# LiPoBattery.net
KiCad netlist of a schematic drawn in Altium Designer
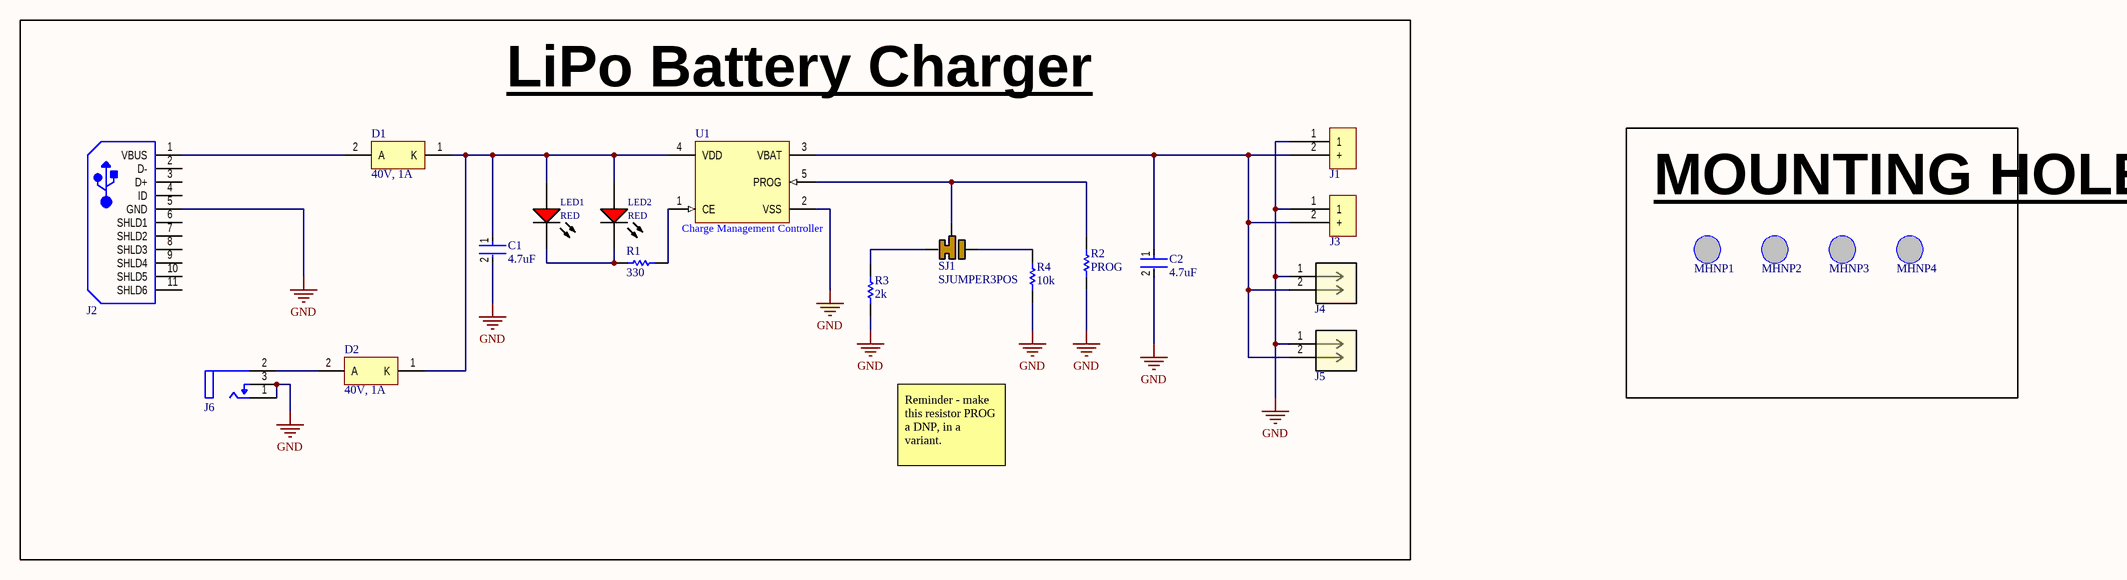
[diagram p0: LiPoBattery.SchDoc]

(export (version "E")
  (design (tool "Eeschema 10.0.6"))
  (components
    (comp (ref "C1")
      (value "4.7uF")
      (footprint "FP-CC0805-0_85-MFG")
      (description "4.7µF ±10% 6.3V Ceramic Capacitor X7R 0805 (2012 Metric)")
      (fields (field (name "MANUFACTURER") "Yageo") (field (name "TOLERANCE") "0.1"))
      (libsource (lib "LiPoBattery_A") (part "CAP CER 4.7UF 6.3V X7R 0805"))
    )
    (comp (ref "C2")
      (value "4.7uF")
      (footprint "FP-CC0805-0_85-MFG")
      (description "4.7µF ±10% 6.3V Ceramic Capacitor X7R 0805 (2012 Metric)")
      (fields (field (name "MANUFACTURER") "Yageo") (field (name "TOLERANCE") "0.1"))
      (libsource (lib "LiPoBattery_A") (part "CAP CER 4.7UF 6.3V X7R 0805"))
    )
    (comp (ref "D1")
      (value "40V, 1A")
      (footprint "ONSC-SMA-2-403D-02_V")
      (description "Schottky Power Rectifier, 2-Pin SMA, Pb-Free, Cut Tape, Diode Schottky 40V 1A Surface Mount SMA")
      (fields (field (name "PARTNUMBER") "MBRA140T3G") (field (name "MANUFACTURER") "ON Semiconductor"))
      (libsource (lib "LiPoBattery_A") (part "DIODE SCHOTTKY 40V 1A SMA"))
    )
    (comp (ref "D2")
      (value "40V, 1A")
      (footprint "ONSC-SMA-2-403D-02_V")
      (description "Schottky Power Rectifier, 2-Pin SMA, Pb-Free, Cut Tape, Diode Schottky 40V 1A Surface Mount SMA")
      (fields (field (name "PARTNUMBER") "MBRA140T3G") (field (name "MANUFACTURER") "ON Semiconductor"))
      (libsource (lib "LiPoBattery_A") (part "DIODE SCHOTTKY 40V 1A SMA"))
    )
    (comp (ref "J1")
      (value "CONN HEADER R/A 2POS 5.08MM")
      (footprint "1-179276-2")
      (description "Connector Header Through Hole, Right Angle 2 position 0.200\" (5.08mm)")
      (fields
        (field (name "MANUFACTURER") "TE Connectivity AMP Connectors")
        (field (name "MANUFACTURER PART NUMBER") "1-179276-2")
      )
      (libsource (lib "LiPoBattery_A") (part "CONN HEADER R/A 2POS 5.08MM"))
    )
    (comp (ref "J2")
      (value "47346-0001")
      (footprint "MOLX-47346-0001-5_V")
      (description "Micro-USB B Receptacle with Flange, -30 to 85 degC, 5-Pin SMD, RoHS, Tape and Reel")
      (fields (field (name "MANUFACTURER") "Molex"))
      (libsource (lib "LiPoBattery_A") (part "CONN RCPT USB2.0 MICRO B SMD R/A"))
    )
    (comp (ref "J3")
      (value "CONN HEADER R/A 2POS 5.08MM")
      (footprint "1-179276-2")
      (description "Connector Header Through Hole, Right Angle 2 position 0.200\" (5.08mm)")
      (fields
        (field (name "MANUFACTURER") "TE Connectivity AMP Connectors")
        (field (name "MANUFACTURER PART NUMBER") "1-179276-2")
      )
      (libsource (lib "LiPoBattery_A") (part "CONN HEADER R/A 2POS 5.08MM"))
    )
    (comp (ref "J4")
      (value "2 POS VERT HEADER 0.100\"")
      (footprint "2Pins_AMP")
      (description "Connector Header Through Hole 2 position")
      (fields
        (field (name "MANUFACTURER PART NUMBER") "67997-402HLF")
        (field (name "MANUFACTURER") "Amphenol ICC (FCI)")
        (field (name "COPYRIGHT") "Copyright (C) 2018 Accelerated Designs. All rights reserved")
      )
      (libsource (lib "LiPoBattery_A") (part "CONN HEADER VERT 2POS 0.100{dblquote}"))
    )
    (comp (ref "J5")
      (value "2 POS VERT HEADER 0.100\"")
      (footprint "2Pins_AMP")
      (description "Connector Header Through Hole 2 position")
      (fields
        (field (name "MANUFACTURER PART NUMBER") "67997-402HLF")
        (field (name "MANUFACTURER") "Amphenol ICC (FCI)")
        (field (name "COPYRIGHT") "Copyright (C) 2018 Accelerated Designs. All rights reserved")
      )
      (libsource (lib "LiPoBattery_A") (part "CONN HEADER VERT 2POS 0.100{dblquote}"))
    )
    (comp (ref "J6")
      (value "CONN PWR JACK 2.1X5.5MM SOLDER")
      (footprint "FP-RASM722PTR13X-MFG")
      (description "Power Barrel Connector Jack 2.10mm ID (0.083\"), 5.50mm OD (0.217\") Surface Mount, Right Angle")
      (fields
        (field (name "MANUFACTURER") "Switchcraft")
        (field (name "MANUFACTURER PART NUMBER") "RASM722PTR13X")
      )
      (libsource (lib "LiPoBattery_A") (part "CONN PWR JACK 2.1X5.5MM SOLDER"))
    )
    (comp (ref "LED1")
      (value "RED")
      (footprint "VISH-TLMS1000_V")
      (description "Low Current LED, 40 mW, 1.8 V, -40 to 100 degC, 2-Pin SMD (0603), RoHS, Tape and Reel")
      (fields
        (field (name "MANUFACTURER") "Vishay")
        (field (name "MANUFACTURER PART NUMBER") "TLMS1000-GS08")
      )
      (libsource (lib "LiPoBattery_A") (part "LED RED 0603 SMD"))
    )
    (comp (ref "LED2")
      (value "RED")
      (footprint "VISH-TLMS1000_V")
      (description "Low Current LED, 40 mW, 1.8 V, -40 to 100 degC, 2-Pin SMD (0603), RoHS, Tape and Reel")
      (fields
        (field (name "MANUFACTURER") "Vishay")
        (field (name "MANUFACTURER PART NUMBER") "TLMS1000-GS08")
      )
      (libsource (lib "LiPoBattery_A") (part "LED RED 0603 SMD"))
    )
    (comp (ref "MHNP1")
      (value "Mounting Hole Non-Plated 3.2mm")
      (footprint "MTHNP3P2MM")
      (description "Mounting Hole Non-Plated 3.2 mm drill hole")
      (libsource (lib "LiPoBattery_A") (part "MTHNP3P2MM"))
    )
    (comp (ref "MHNP2")
      (value "Mounting Hole Non-Plated 3.2mm")
      (footprint "MTHNP3P2MM")
      (description "Mounting Hole Non-Plated 3.2 mm drill hole")
      (libsource (lib "LiPoBattery_A") (part "MTHNP3P2MM"))
    )
    (comp (ref "MHNP3")
      (value "Mounting Hole Non-Plated 3.2mm")
      (footprint "MTHNP3P2MM")
      (description "Mounting Hole Non-Plated 3.2 mm drill hole")
      (libsource (lib "LiPoBattery_A") (part "MTHNP3P2MM"))
    )
    (comp (ref "MHNP4")
      (value "Mounting Hole Non-Plated 3.2mm")
      (footprint "MTHNP3P2MM")
      (description "Mounting Hole Non-Plated 3.2 mm drill hole")
      (libsource (lib "LiPoBattery_A") (part "MTHNP3P2MM"))
    )
    (comp (ref "R1")
      (value "330")
      (footprint "RESC2013X50X30NL20T20")
      (description "330 Ohms ±1% 0.125W, 1/8W Chip Resistor 0805 (2012 Metric) Automotive AEC-Q200 Thick Film")
      (fields
        (field (name "MANUFACTURER") "Vishay")
        (field (name "MANUFACTURER PART NUMBER") "CRCW0805330RFKEA")
      )
      (libsource (lib "LiPoBattery_A") (part "RES SMD 330 OHM 1% 1/8W 0805"))
    )
    (comp (ref "R2")
      (value "PROG")
      (footprint "VISH-A1-2_V2")
      (fields
        (field (name "TOLERANCE") "+/-5%")
        (field (name "POWER") "2 W")
        (field (name "PARTNUMBER") "PR02000206202JA100")
      )
      (libsource (lib "LiPoBattery_A") (part "RES 62K OHM 2W 5% AXIAL"))
    )
    (comp (ref "R3")
      (value "2k")
      (footprint "RESC2013X70X40ML20T20")
      (description "2 kOhms ±5% 0.125W, 1/8W Chip Resistor 0805 (2012 Metric) Automotive AEC-Q200 Thick Film")
      (fields
        (field (name "MANUFACTURER") "Panasonic")
        (field (name "MANUFACTURER PART NUMBER") "ERJ-6GEYJ202V")
      )
      (libsource (lib "LiPoBattery_A") (part "RES SMD 2K OHM 5% 1/8W 0805"))
    )
    (comp (ref "R4")
      (value "10k")
      (footprint "RESC2013X70X40ML20T20")
      (description "10 kOhms ±1% 0.125W, 1/8W Chip Resistor 0805 (2012 Metric) Automotive AEC-Q200 Thick Film")
      (fields
        (field (name "MANUFACTURER") "Panasonic")
        (field (name "MANUFACTURER PART NUMBER") "ERJ-6ENF1002V")
      )
      (libsource (lib "LiPoBattery_A") (part "RES SMD 10K OHM 1% 1/8W 0805"))
    )
    (comp (ref "SJ1")
      (value "SJUMPER3POS")
      (footprint "SJUMPER3POS-Footprint-1")
      (description "Solder jumper 3 pads and pins")
      (libsource (lib "LiPoBattery_A") (part "SJUMPER3POS"))
    )
    (comp (ref "U1")
      (value "Charge Management Controller")
      (footprint "SOT-23-OT5_M")
      (fields
        (field (name "MANUFACTURER") "Microchip")
        (field (name "MANUFACTURER PART NUMBER") "MCP73811T-420I/OT")
      )
      (libsource (lib "LiPoBattery_A") (part "IC LI-ION/LI-POLY CTRLR SOT23-5"))
    )
  )
  (nets
    (net (code "1") (name "GND") (class "Default")
      (node (ref "C1") (pin "2") (pinfunction "2_2") (pintype "passive"))
      (node (ref "C2") (pin "2") (pinfunction "2_2") (pintype "passive"))
      (node (ref "J1") (pin "1") (pinfunction "1_1") (pintype "passive"))
      (node (ref "J2") (pin "5") (pinfunction "GND_5") (pintype "passive"))
      (node (ref "J3") (pin "1") (pinfunction "1_1") (pintype "passive"))
      (node (ref "J4") (pin "1") (pinfunction "1_1") (pintype "passive"))
      (node (ref "J5") (pin "1") (pinfunction "1_1") (pintype "passive"))
      (node (ref "J6") (pin "1") (pinfunction "TIP_TERMINAL(CENTER_PIN)_1") (pintype "passive"))
      (node (ref "J6") (pin "3") (pinfunction "SHUNT_TERMINAL_3") (pintype "passive"))
      (node (ref "R2") (pin "1") (pinfunction "1_1") (pintype "passive"))
      (node (ref "R3") (pin "2") (pinfunction "2_2") (pintype "passive"))
      (node (ref "R4") (pin "1") (pinfunction "1_1") (pintype "passive"))
      (node (ref "U1") (pin "2") (pinfunction "VSS_2") (pintype "power_in"))
    )
    (net (code "2") (name "Net-(D1-A)") (class "Default")
      (node (ref "D1") (pin "2") (pinfunction "A_2") (pintype "passive"))
      (node (ref "J2") (pin "1") (pinfunction "VBUS_1") (pintype "passive"))
    )
    (net (code "3") (name "Net-(D1-K)") (class "Default")
      (node (ref "C1") (pin "1") (pinfunction "1_1") (pintype "passive"))
      (node (ref "D1") (pin "1") (pinfunction "K_1") (pintype "passive"))
      (node (ref "D2") (pin "1") (pinfunction "K_1") (pintype "passive"))
      (node (ref "LED1") (pin "1") (pinfunction "A_1") (pintype "passive"))
      (node (ref "LED2") (pin "1") (pinfunction "A_1") (pintype "passive"))
      (node (ref "U1") (pin "4") (pinfunction "VDD_4") (pintype "power_in"))
    )
    (net (code "4") (name "Net-(D2-A)") (class "Default")
      (node (ref "D2") (pin "2") (pinfunction "A_2") (pintype "passive"))
      (node (ref "J6") (pin "2") (pinfunction "SLEEVE_TERMINAL_2") (pintype "passive"))
    )
    (net (code "5") (name "Net-(J1-+)") (class "Default")
      (node (ref "C2") (pin "1") (pinfunction "1_1") (pintype "passive"))
      (node (ref "J1") (pin "2") (pinfunction "+_2") (pintype "passive"))
      (node (ref "J3") (pin "2") (pinfunction "+_2") (pintype "passive"))
      (node (ref "J4") (pin "2") (pinfunction "2_2") (pintype "passive"))
      (node (ref "J5") (pin "2") (pinfunction "2_2") (pintype "passive"))
      (node (ref "U1") (pin "3") (pinfunction "VBAT_3") (pintype "power_in"))
    )
    (net (code "6") (name "Net-(LED1-K)") (class "Default")
      (node (ref "LED1") (pin "2") (pinfunction "K_2") (pintype "passive"))
      (node (ref "LED2") (pin "2") (pinfunction "K_2") (pintype "passive"))
      (node (ref "R1") (pin "1") (pinfunction "1_1") (pintype "passive"))
    )
    (net (code "7") (name "Net-(R3-Pad1)") (class "Default")
      (node (ref "R3") (pin "1") (pinfunction "1_1") (pintype "passive"))
      (node (ref "SJ1") (pin "1") (pinfunction "1_1") (pintype "passive"))
    )
    (net (code "8") (name "Net-(R4-Pad2)") (class "Default")
      (node (ref "R4") (pin "2") (pinfunction "2_2") (pintype "passive"))
      (node (ref "SJ1") (pin "3") (pinfunction "3_3") (pintype "passive"))
    )
    (net (code "9") (name "Net-(U1-CE)") (class "Default")
      (node (ref "R1") (pin "2") (pinfunction "2_2") (pintype "passive"))
      (node (ref "U1") (pin "1") (pinfunction "CE_1") (pintype "input"))
    )
    (net (code "10") (name "Net-(U1-PROG)") (class "Default")
      (node (ref "R2") (pin "2") (pinfunction "2_2") (pintype "passive"))
      (node (ref "SJ1") (pin "2") (pinfunction "2_2") (pintype "passive"))
      (node (ref "U1") (pin "5") (pinfunction "PROG_5") (pintype "input"))
    )
    (net (code "11") (name "unconnected-(J2-D+-Pad3)") (class "Default")
      (node (ref "J2") (pin "3") (pinfunction "D+_3") (pintype "passive"))
    )
    (net (code "12") (name "unconnected-(J2-D--Pad2)") (class "Default")
      (node (ref "J2") (pin "2") (pinfunction "D-_2") (pintype "passive"))
    )
    (net (code "13") (name "unconnected-(J2-ID-Pad4)") (class "Default")
      (node (ref "J2") (pin "4") (pinfunction "ID_4") (pintype "passive"))
    )
    (net (code "14") (name "unconnected-(J2-SHLD1-Pad6)") (class "Default")
      (node (ref "J2") (pin "6") (pinfunction "SHLD1_6") (pintype "passive"))
    )
    (net (code "15") (name "unconnected-(J2-SHLD2-Pad7)") (class "Default")
      (node (ref "J2") (pin "7") (pinfunction "SHLD2_7") (pintype "passive"))
    )
    (net (code "16") (name "unconnected-(J2-SHLD3-Pad8)") (class "Default")
      (node (ref "J2") (pin "8") (pinfunction "SHLD3_8") (pintype "passive"))
    )
    (net (code "17") (name "unconnected-(J2-SHLD4-Pad9)") (class "Default")
      (node (ref "J2") (pin "9") (pinfunction "SHLD4_9") (pintype "passive"))
    )
    (net (code "18") (name "unconnected-(J2-SHLD5-Pad10)") (class "Default")
      (node (ref "J2") (pin "10") (pinfunction "SHLD5_10") (pintype "passive"))
    )
    (net (code "19") (name "unconnected-(J2-SHLD6-Pad11)") (class "Default")
      (node (ref "J2") (pin "11") (pinfunction "SHLD6_11") (pintype "passive"))
    )
  )
)
